# LT3042.net
KiCad netlist of a schematic drawn in EAGLE
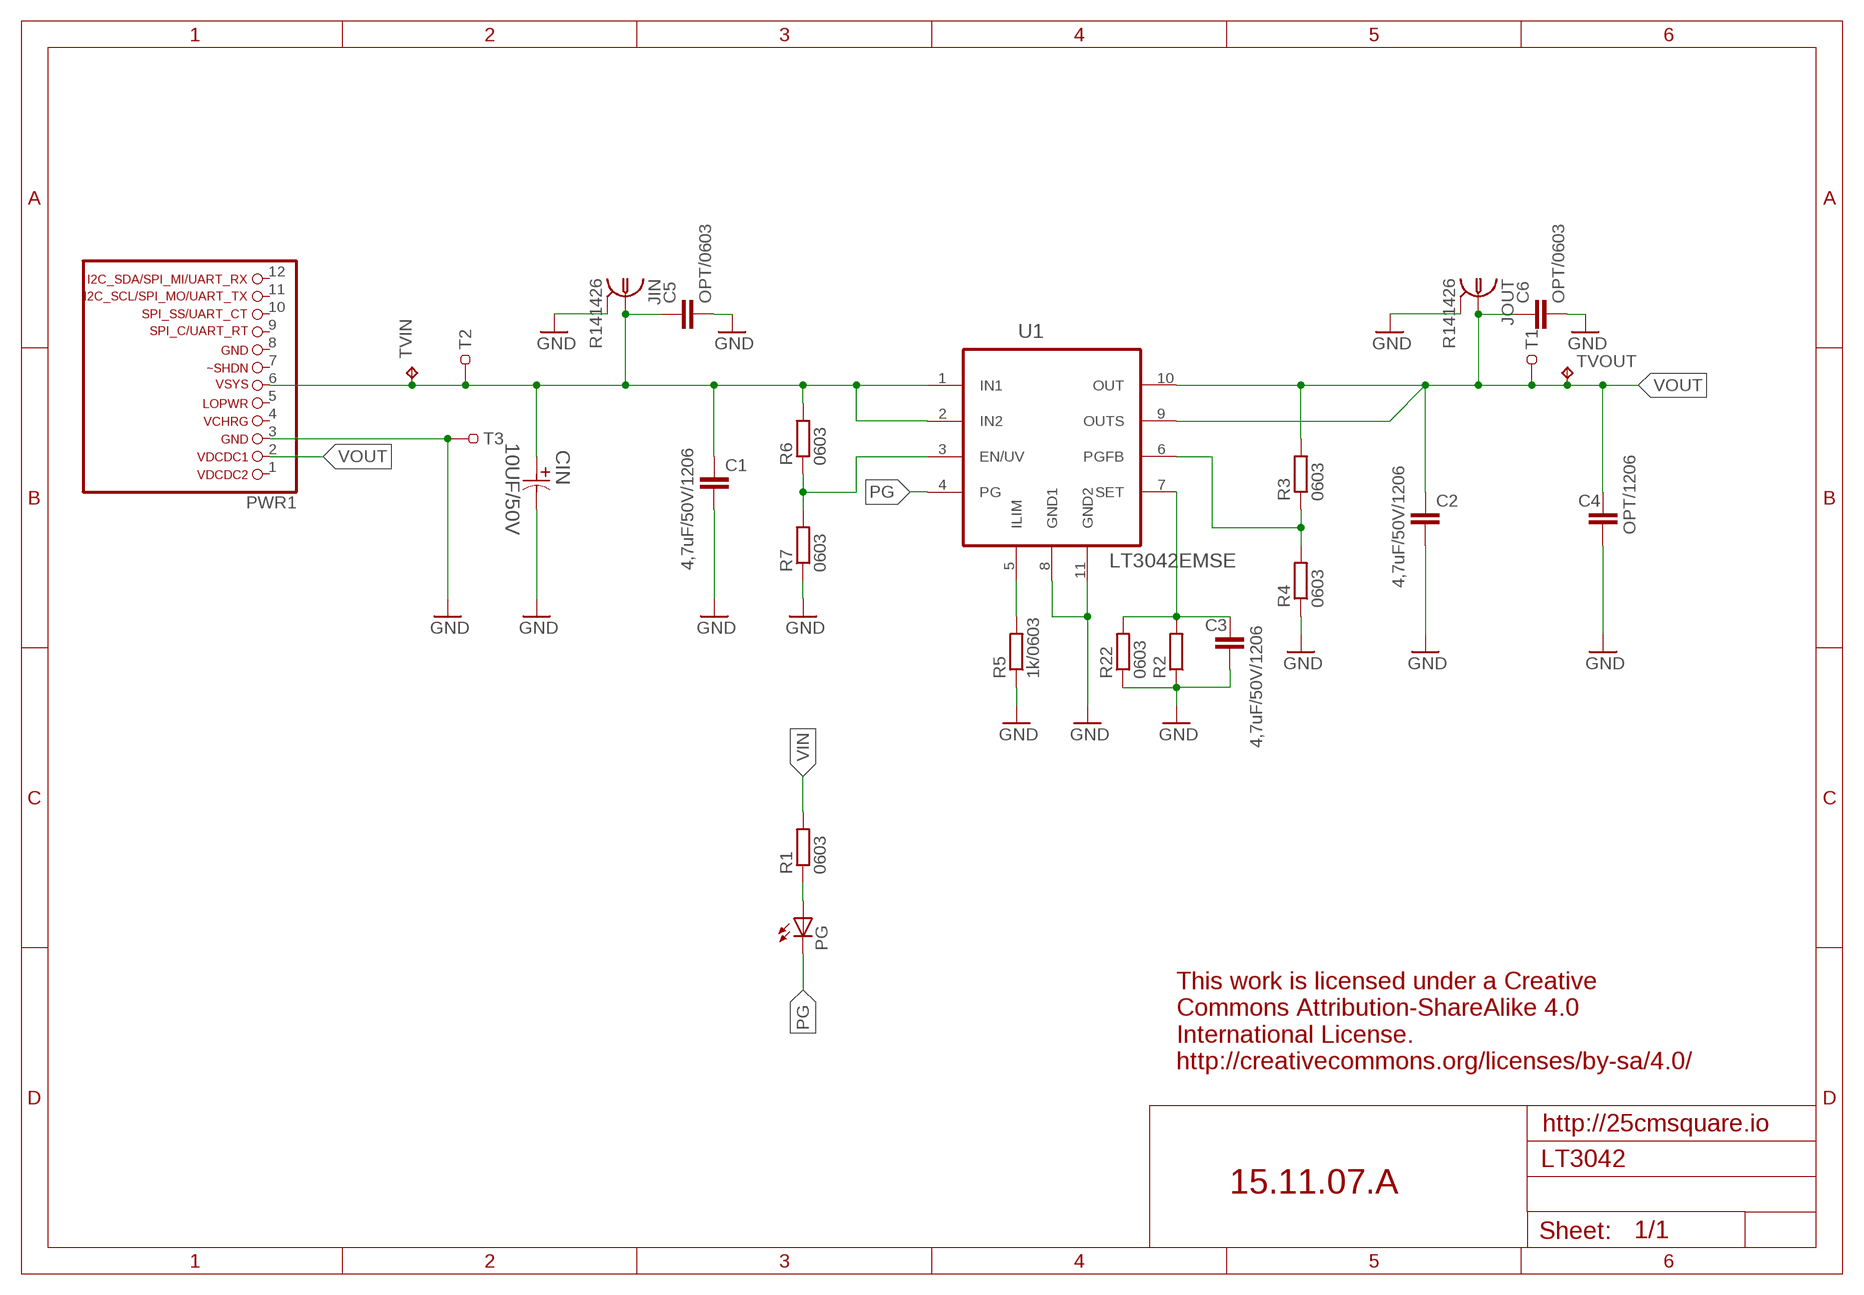
[diagram p0: schematic, sheet 1]

(export (version "E")
  (design (tool "Eeschema 10.0.6"))
  (components
    (comp (ref "C1")
      (value "4,7uF/50V/1206")
      (footprint "eagle-import:C1206K")
      (libsource (lib "eagle-import") (part "C-EUC1206K"))
    )
    (comp (ref "C2")
      (value "4,7uF/50V/1206")
      (footprint "eagle-import:C1206K")
      (libsource (lib "eagle-import") (part "C-EUC1206K"))
    )
    (comp (ref "C3")
      (value "4,7uF/50V/1206")
      (footprint "eagle-import:C1206K")
      (libsource (lib "eagle-import") (part "C-EUC1206K"))
    )
    (comp (ref "C4")
      (value "OPT/1206")
      (footprint "eagle-import:C1206K")
      (libsource (lib "eagle-import") (part "C-EUC1206K"))
    )
    (comp (ref "C5")
      (value "OPT/0603")
      (footprint "eagle-import:C0603K")
      (libsource (lib "eagle-import") (part "C-EUC0603K"))
    )
    (comp (ref "C6")
      (value "OPT/0603")
      (footprint "eagle-import:C0603K")
      (libsource (lib "eagle-import") (part "C-EUC0603K"))
    )
    (comp (ref "CIN")
      (value "10UF/50V")
      (footprint "eagle-import:CAPAE530X610N")
      (fields (field (name "MPN") "EEE-FK1H100UR") (field (name "TOLERANCE") "±20 %"))
      (libsource (lib "eagle-import") (part "EEE--CASE-CFK1H100UR"))
    )
    (comp (ref "JIN")
      (value "R141426")
      (footprint "eagle-import:R141426")
      (fields (field (name "MF") "FARNELL") (field (name "MPN") "R141426161"))
      (libsource (lib "eagle-import") (part "R141426"))
    )
    (comp (ref "JOUT")
      (value "R141426")
      (footprint "eagle-import:R141426")
      (fields (field (name "MF") "FARNELL") (field (name "MPN") "R141426161"))
      (libsource (lib "eagle-import") (part "R141426"))
    )
    (comp (ref "PG")
      (value "LEDSML0603")
      (footprint "eagle-import:SML0603")
      (libsource (lib "eagle-import") (part "LEDSML0603"))
    )
    (comp (ref "PWR1")
      (value "LIWE_12_PIN_PWR")
      (footprint "eagle-import:LIWE_12_PIN")
      (libsource (lib "eagle-import") (part "LIWE_12_PIN_PWR"))
    )
    (comp (ref "R1")
      (value "0603")
      (footprint "eagle-import:R0603")
      (libsource (lib "eagle-import") (part "R-EU_R0603"))
    )
    (comp (ref "R2")
      (value "R-EU_0309_10")
      (footprint "eagle-import:0309_10")
      (libsource (lib "eagle-import") (part "R-EU_0309_10"))
    )
    (comp (ref "R3")
      (value "0603")
      (footprint "eagle-import:R0603")
      (libsource (lib "eagle-import") (part "R-EU_R0603"))
    )
    (comp (ref "R4")
      (value "0603")
      (footprint "eagle-import:R0603")
      (libsource (lib "eagle-import") (part "R-EU_R0603"))
    )
    (comp (ref "R5")
      (value "1k/0603")
      (footprint "eagle-import:R0603")
      (libsource (lib "eagle-import") (part "R-EU_R0603"))
    )
    (comp (ref "R6")
      (value "0603")
      (footprint "eagle-import:R0603")
      (libsource (lib "eagle-import") (part "R-EU_R0603"))
    )
    (comp (ref "R7")
      (value "0603")
      (footprint "eagle-import:R0603")
      (libsource (lib "eagle-import") (part "R-EU_R0603"))
    )
    (comp (ref "R22")
      (value "0603")
      (footprint "eagle-import:R0603")
      (libsource (lib "eagle-import") (part "R-EU_R0603"))
    )
    (comp (ref "T1")
      (value "TEST-22-MULTICOMP")
      (footprint "eagle-import:TEST_1MM")
      (libsource (lib "eagle-import") (part "TEST-22-MULTICOMP"))
    )
    (comp (ref "T2")
      (value "TEST-22-MULTICOMP")
      (footprint "eagle-import:TEST_1MM")
      (libsource (lib "eagle-import") (part "TEST-22-MULTICOMP"))
    )
    (comp (ref "T3")
      (value "TEST-22-MULTICOMP")
      (footprint "eagle-import:TEST_1MM")
      (libsource (lib "eagle-import") (part "TEST-22-MULTICOMP"))
    )
    (comp (ref "TVIN")
      (value "TPTP14R")
      (footprint "eagle-import:TP14R")
      (libsource (lib "eagle-import") (part "TPTP14R"))
    )
    (comp (ref "TVOUT")
      (value "TPTP14R")
      (footprint "eagle-import:TP14R")
      (libsource (lib "eagle-import") (part "TPTP14R"))
    )
    (comp (ref "U1")
      (value "LT3042EMSE")
      (footprint "eagle-import:MSOP10-EPAD")
      (libsource (lib "eagle-import") (part "LT3042EMSE"))
    )
  )
  (nets
    (net (code "1") (name "GND") (class "Default")
      (node (ref "C1") (pin "2") (pinfunction "2_2") (pintype "passive"))
      (node (ref "C2") (pin "2") (pinfunction "2_2") (pintype "passive"))
      (node (ref "C3") (pin "2") (pinfunction "2_2") (pintype "passive"))
      (node (ref "C4") (pin "2") (pinfunction "2_2") (pintype "passive"))
      (node (ref "C5") (pin "2") (pinfunction "2_2") (pintype "passive"))
      (node (ref "C6") (pin "2") (pinfunction "2_2") (pintype "passive"))
      (node (ref "CIN") (pin "2") (pinfunction "2_2") (pintype "passive"))
      (node (ref "JIN") (pin "2") (pinfunction "2_2") (pintype "passive"))
      (node (ref "JIN") (pin "3") (pinfunction "2_3") (pintype "passive"))
      (node (ref "JIN") (pin "4") (pinfunction "2_4") (pintype "passive"))
      (node (ref "JIN") (pin "5") (pinfunction "2_5") (pintype "passive"))
      (node (ref "JOUT") (pin "2") (pinfunction "2_2") (pintype "passive"))
      (node (ref "JOUT") (pin "3") (pinfunction "2_3") (pintype "passive"))
      (node (ref "JOUT") (pin "4") (pinfunction "2_4") (pintype "passive"))
      (node (ref "JOUT") (pin "5") (pinfunction "2_5") (pintype "passive"))
      (node (ref "PWR1") (pin "3") (pinfunction "3_3") (pintype "passive"))
      (node (ref "R2") (pin "1") (pinfunction "1_1") (pintype "passive"))
      (node (ref "R22") (pin "1") (pinfunction "1_1") (pintype "passive"))
      (node (ref "R4") (pin "1") (pinfunction "1_1") (pintype "passive"))
      (node (ref "R5") (pin "1") (pinfunction "1_1") (pintype "passive"))
      (node (ref "R7") (pin "1") (pinfunction "1_1") (pintype "passive"))
      (node (ref "T3") (pin "1") (pinfunction "1_1") (pintype "passive"))
      (node (ref "U1") (pin "11") (pinfunction "GND2_11") (pintype "power_in"))
      (node (ref "U1") (pin "8") (pinfunction "GND1_8") (pintype "power_in"))
    )
    (net (code "2") (name "Net-(PG-PadA)") (class "Default")
      (node (ref "PG") (pin "A") (pinfunction "A_A") (pintype "passive"))
      (node (ref "R1") (pin "1") (pinfunction "1_1") (pintype "passive"))
    )
    (net (code "3") (name "Net-(U1-EN{slash}UV)") (class "Default")
      (node (ref "R6") (pin "1") (pinfunction "1_1") (pintype "passive"))
      (node (ref "R7") (pin "2") (pinfunction "2_2") (pintype "passive"))
      (node (ref "U1") (pin "3") (pinfunction "EN/UV_3") (pintype "input"))
    )
    (net (code "4") (name "Net-(U1-ILIM)") (class "Default")
      (node (ref "R5") (pin "2") (pinfunction "2_2") (pintype "passive"))
      (node (ref "U1") (pin "5") (pinfunction "ILIM_5") (pintype "passive"))
    )
    (net (code "5") (name "Net-(U1-PGFB)") (class "Default")
      (node (ref "R3") (pin "1") (pinfunction "1_1") (pintype "passive"))
      (node (ref "R4") (pin "2") (pinfunction "2_2") (pintype "passive"))
      (node (ref "U1") (pin "6") (pinfunction "PGFB_6") (pintype "input"))
    )
    (net (code "6") (name "Net-(U1-SET)") (class "Default")
      (node (ref "C3") (pin "1") (pinfunction "1_1") (pintype "passive"))
      (node (ref "R2") (pin "2") (pinfunction "2_2") (pintype "passive"))
      (node (ref "R22") (pin "2") (pinfunction "2_2") (pintype "passive"))
      (node (ref "U1") (pin "7") (pinfunction "SET_7") (pintype "input"))
    )
    (net (code "7") (name "PG") (class "Default")
      (node (ref "PG") (pin "C") (pinfunction "C_C") (pintype "passive"))
      (node (ref "U1") (pin "4") (pinfunction "PG_4") (pintype "output"))
    )
    (net (code "8") (name "VIN") (class "Default")
      (node (ref "C1") (pin "1") (pinfunction "1_1") (pintype "passive"))
      (node (ref "C5") (pin "1") (pinfunction "1_1") (pintype "passive"))
      (node (ref "CIN") (pin "1") (pinfunction "1_1") (pintype "passive"))
      (node (ref "JIN") (pin "1") (pinfunction "1_1") (pintype "passive"))
      (node (ref "PWR1") (pin "6") (pinfunction "6_6") (pintype "passive"))
      (node (ref "R1") (pin "2") (pinfunction "2_2") (pintype "passive"))
      (node (ref "R6") (pin "2") (pinfunction "2_2") (pintype "passive"))
      (node (ref "T2") (pin "1") (pinfunction "1_1") (pintype "passive"))
      (node (ref "TVIN") (pin "TP") (pinfunction "TP_TP") (pintype "input"))
      (node (ref "U1") (pin "1") (pinfunction "IN1_1") (pintype "power_in"))
      (node (ref "U1") (pin "2") (pinfunction "IN2_2") (pintype "power_in"))
    )
    (net (code "9") (name "VOUT") (class "Default")
      (node (ref "C2") (pin "1") (pinfunction "1_1") (pintype "passive"))
      (node (ref "C4") (pin "1") (pinfunction "1_1") (pintype "passive"))
      (node (ref "C6") (pin "1") (pinfunction "1_1") (pintype "passive"))
      (node (ref "JOUT") (pin "1") (pinfunction "1_1") (pintype "passive"))
      (node (ref "PWR1") (pin "2") (pinfunction "2_2") (pintype "passive"))
      (node (ref "R3") (pin "2") (pinfunction "2_2") (pintype "passive"))
      (node (ref "T1") (pin "1") (pinfunction "1_1") (pintype "passive"))
      (node (ref "TVOUT") (pin "TP") (pinfunction "TP_TP") (pintype "input"))
      (node (ref "U1") (pin "10") (pinfunction "OUT_10") (pintype "power_in"))
      (node (ref "U1") (pin "9") (pinfunction "OUTS_9") (pintype "input"))
    )
    (net (code "10") (name "unconnected-(PWR1-Pad1)") (class "Default")
      (node (ref "PWR1") (pin "1") (pinfunction "1_1") (pintype "passive"))
    )
    (net (code "11") (name "unconnected-(PWR1-Pad4)") (class "Default")
      (node (ref "PWR1") (pin "4") (pinfunction "4_4") (pintype "passive"))
    )
    (net (code "12") (name "unconnected-(PWR1-Pad5)") (class "Default")
      (node (ref "PWR1") (pin "5") (pinfunction "5_5") (pintype "passive"))
    )
    (net (code "13") (name "unconnected-(PWR1-Pad7)") (class "Default")
      (node (ref "PWR1") (pin "7") (pinfunction "7_7") (pintype "passive"))
    )
    (net (code "14") (name "unconnected-(PWR1-Pad8)") (class "Default")
      (node (ref "PWR1") (pin "8") (pinfunction "8_8") (pintype "passive"))
    )
    (net (code "15") (name "unconnected-(PWR1-Pad9)") (class "Default")
      (node (ref "PWR1") (pin "9") (pinfunction "9_9") (pintype "passive"))
    )
    (net (code "16") (name "unconnected-(PWR1-Pad10)") (class "Default")
      (node (ref "PWR1") (pin "10") (pinfunction "10_10") (pintype "passive"))
    )
    (net (code "17") (name "unconnected-(PWR1-Pad11)") (class "Default")
      (node (ref "PWR1") (pin "11") (pinfunction "11_11") (pintype "passive"))
    )
    (net (code "18") (name "unconnected-(PWR1-Pad12)") (class "Default")
      (node (ref "PWR1") (pin "12") (pinfunction "12_12") (pintype "passive"))
    )
  )
)
